# MilliNut.net
KiCad netlist of a schematic drawn in Altium Designer
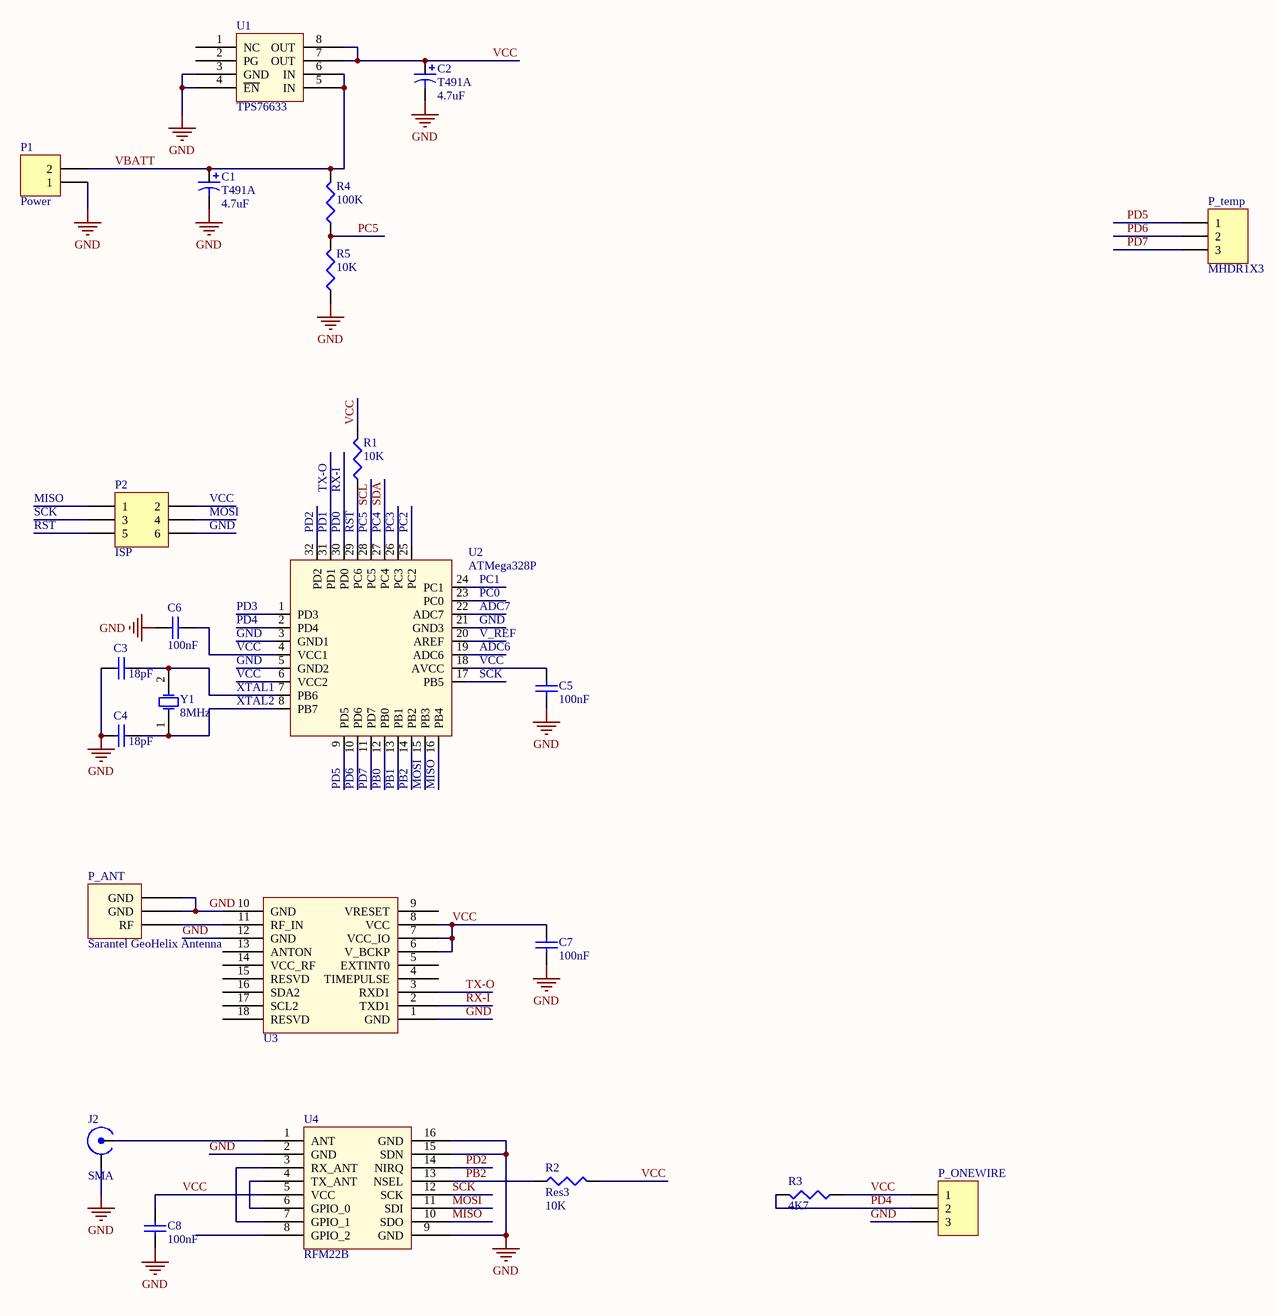
[diagram p0: MilliNut.SchDoc]

(export (version "E")
  (design (tool "Eeschema 10.0.6"))
  (components
    (comp (ref "C1")
      (value "T491A")
      (footprint "Kemet T491A")
      (description "Solid Tantalum Chip Capacitor, Standard T491 Series - Industrial Grade")
      (fields (field (name "ALTIUM_VALUE") "4.7uF") (field (name "PUBLISHER") "Altium Limited"))
      (libsource (lib "KEMET Chip Capacitor") (part "T491A"))
    )
    (comp (ref "C2")
      (value "T491A")
      (footprint "Kemet T491A")
      (description "Solid Tantalum Chip Capacitor, Standard T491 Series - Industrial Grade")
      (fields (field (name "ALTIUM_VALUE") "4.7uF") (field (name "PUBLISHER") "Altium Limited"))
      (libsource (lib "KEMET Chip Capacitor") (part "T491A"))
    )
    (comp (ref "C3")
      (value "18pF")
      (footprint "1608[0603]")
      (description "Ceramic Chip Capacitor - Standard")
      (fields (field (name "Comment") "C0805") (field (name "PUBLISHER") "Altium Limited"))
      (libsource (lib "KEMET Chip Capacitor") (part "C0805"))
    )
    (comp (ref "C4")
      (value "18pF")
      (footprint "1608[0603]")
      (description "Ceramic Chip Capacitor - Standard")
      (fields (field (name "Comment") "C0805") (field (name "PUBLISHER") "Altium Limited"))
      (libsource (lib "KEMET Chip Capacitor") (part "C0805"))
    )
    (comp (ref "C5")
      (value "100nF")
      (footprint "1608[0603]")
      (description "Capacitor (Semiconductor SIM Model)")
      (fields (field (name "Comment") "Cap Semi") (field (name "PUBLISHER") "Altium Limited"))
      (libsource (lib "Miscellaneous Devices") (part "Cap Semi"))
    )
    (comp (ref "C6")
      (value "100nF")
      (footprint "1608[0603]")
      (description "Capacitor (Semiconductor SIM Model)")
      (fields (field (name "Comment") "Cap Semi") (field (name "PUBLISHER") "Altium Limited"))
      (libsource (lib "Miscellaneous Devices") (part "Cap Semi"))
    )
    (comp (ref "C7")
      (value "100nF")
      (footprint "1608[0603]")
      (description "Capacitor (Semiconductor SIM Model)")
      (fields (field (name "Comment") "Cap Semi") (field (name "PUBLISHER") "Altium Limited"))
      (libsource (lib "Miscellaneous Devices") (part "Cap Semi"))
    )
    (comp (ref "C8")
      (value "100nF")
      (footprint "1608[0603]")
      (description "Capacitor (Semiconductor SIM Model)")
      (fields (field (name "Comment") "Cap Semi") (field (name "PUBLISHER") "Altium Limited"))
      (libsource (lib "Miscellaneous Devices") (part "Cap Semi"))
    )
    (comp (ref "J2")
      (value "SMA")
      (footprint "Darkside_Lib:CON SMA PCB 90")
      (description "Power Connector")
      (fields (field (name "Comment") "SMA_L"))
      (libsource (lib "Darkside_Lib") (part "SMA_L"))
    )
    (comp (ref "P1")
      (value "Power")
      (footprint "HDR1X2")
      (description "Header, 2-Pin")
      (fields (field (name "PUBLISHER") "Altium Limited"))
      (libsource (lib "Miscellaneous Connectors") (part "Header 2"))
    )
    (comp (ref "P2")
      (value "ISP")
      (footprint "HDR2X3")
      (description "Header, 3-Pin, Dual row")
      (fields (field (name "PUBLISHER") "Altium Limited"))
      (libsource (lib "Miscellaneous Connectors") (part "Header 3X2"))
    )
    (comp (ref "P_ANT")
      (value "Sarantel GeoHelix Antenna")
      (footprint "Darkside_Lib:Sarantel SL1202RH")
      (libsource (lib "Darkside_Lib") (part "Sarantel GeoHelix Antenna"))
    )
    (comp (ref "P_ONEWIRE")
      (value "Header 3")
      (footprint "HDR1X3")
      (description "Header, 3-Pin")
      (fields (field (name "PUBLISHER") "Altium Limited"))
      (libsource (lib "Miscellaneous Connectors") (part "Header 3"))
    )
    (comp (ref "P_temp")
      (value "MHDR1X3")
      (footprint "MHDR1X3")
      (description "Header, 3-Pin")
      (fields (field (name "PUBLISHER") "Altium Limited"))
      (libsource (lib "Miscellaneous Connectors") (part "MHDR1X3"))
    )
    (comp (ref "R1")
      (value "10K")
      (footprint "1608[0603]")
      (description "Resistor")
      (fields (field (name "Comment") "Res3") (field (name "PUBLISHER") "Altium Limited"))
      (libsource (lib "Miscellaneous Devices") (part "Res3"))
    )
    (comp (ref "R2")
      (value "Res3")
      (footprint "J1-0603")
      (description "Resistor")
      (fields (field (name "ALTIUM_VALUE") "10K") (field (name "PUBLISHER") "Altium Limited"))
      (libsource (lib "Miscellaneous Devices") (part "Res3"))
    )
    (comp (ref "R3")
      (value "4K7")
      (footprint "J1-0603")
      (description "Resistor")
      (fields (field (name "Comment") "Res3") (field (name "PUBLISHER") "Altium Limited"))
      (libsource (lib "Miscellaneous Devices") (part "Res3"))
    )
    (comp (ref "R4")
      (value "100K")
      (footprint "J1-0603")
      (description "Resistor")
      (fields (field (name "Comment") "Res3") (field (name "PUBLISHER") "Altium Limited"))
      (libsource (lib "Miscellaneous Devices") (part "Res3"))
    )
    (comp (ref "R5")
      (value "10K")
      (footprint "J1-0603")
      (description "Resistor")
      (fields (field (name "Comment") "Res3") (field (name "PUBLISHER") "Altium Limited"))
      (libsource (lib "Miscellaneous Devices") (part "Res3"))
    )
    (comp (ref "U1")
      (value "TPS76633")
      (footprint "TPS76633")
      (libsource (lib "Darkside_Lib") (part "TPS76633"))
    )
    (comp (ref "U2")
      (value "ATMega328P")
      (footprint "Darkside_Lib:TQFP32")
      (libsource (lib "Darkside_Lib") (part "ATMega328P"))
    )
    (comp (ref "U3")
      (value "uBlox MAX-6Q")
      (footprint "MAX-6Q")
      (libsource (lib "Darkside_Lib") (part "uBlox MAX-6Q"))
    )
    (comp (ref "U4")
      (value "RFM22B")
      (footprint "RFM22B")
      (libsource (lib "Darkside_Lib") (part "RFM22B-S2"))
    )
    (comp (ref "Y1")
      (value "8MHz")
      (footprint "ABM3_XTAL")
      (description "Crystal Oscillator")
      (fields (field (name "PUBLISHER") "Altium Limited"))
      (libsource (lib "ECS Crystal Oscillator") (part "ECS-110-S-1"))
    )
  )
  (nets
    (net (code "1") (name "/ADC6") (class "Default")
      (node (ref "U2") (pin "19") (pinfunction "ADC6_19") (pintype "passive"))
    )
    (net (code "2") (name "/ADC7") (class "Default")
      (node (ref "U2") (pin "22") (pinfunction "ADC7_22") (pintype "passive"))
    )
    (net (code "3") (name "/MISO") (class "Default")
      (node (ref "P2") (pin "1") (pinfunction "1_1") (pintype "passive"))
      (node (ref "U2") (pin "16") (pinfunction "PB4_16") (pintype "passive"))
      (node (ref "U4") (pin "10") (pinfunction "SDO_10") (pintype "passive"))
    )
    (net (code "4") (name "/MOSI") (class "Default")
      (node (ref "P2") (pin "4") (pinfunction "4_4") (pintype "passive"))
      (node (ref "U2") (pin "15") (pinfunction "PB3_15") (pintype "passive"))
      (node (ref "U4") (pin "11") (pinfunction "SDI_11") (pintype "passive"))
    )
    (net (code "5") (name "/PB0") (class "Default")
      (node (ref "U2") (pin "12") (pinfunction "PB0_12") (pintype "passive"))
    )
    (net (code "6") (name "/PB1") (class "Default")
      (node (ref "U2") (pin "13") (pinfunction "PB1_13") (pintype "passive"))
    )
    (net (code "7") (name "/PB2") (class "Default")
      (node (ref "R2") (pin "1") (pinfunction "1_1") (pintype "passive"))
      (node (ref "U2") (pin "14") (pinfunction "PB2_14") (pintype "passive"))
      (node (ref "U4") (pin "13") (pinfunction "NSEL_13") (pintype "passive"))
    )
    (net (code "8") (name "/PC0") (class "Default")
      (node (ref "U2") (pin "23") (pinfunction "PC0_23") (pintype "passive"))
    )
    (net (code "9") (name "/PC1") (class "Default")
      (node (ref "U2") (pin "24") (pinfunction "PC1_24") (pintype "passive"))
    )
    (net (code "10") (name "/PC2") (class "Default")
      (node (ref "U2") (pin "25") (pinfunction "PC2_25") (pintype "passive"))
    )
    (net (code "11") (name "/PC3") (class "Default")
      (node (ref "U2") (pin "26") (pinfunction "PC3_26") (pintype "passive"))
    )
    (net (code "12") (name "/PC4") (class "Default")
      (node (ref "U2") (pin "27") (pinfunction "PC4_27") (pintype "passive"))
    )
    (net (code "13") (name "/PC5") (class "Default")
      (node (ref "R4") (pin "1") (pinfunction "1_1") (pintype "passive"))
      (node (ref "R5") (pin "2") (pinfunction "2_2") (pintype "passive"))
      (node (ref "U2") (pin "28") (pinfunction "PC5_28") (pintype "passive"))
    )
    (net (code "14") (name "/PD0") (class "Default")
      (node (ref "U2") (pin "30") (pinfunction "PD0_30") (pintype "passive"))
      (node (ref "U3") (pin "2") (pinfunction "TXD1_2") (pintype "passive"))
    )
    (net (code "15") (name "/PD1") (class "Default")
      (node (ref "U2") (pin "31") (pinfunction "PD1_31") (pintype "passive"))
      (node (ref "U3") (pin "3") (pinfunction "RXD1_3") (pintype "passive"))
    )
    (net (code "16") (name "/PD2") (class "Default")
      (node (ref "U2") (pin "32") (pinfunction "PD2_32") (pintype "passive"))
      (node (ref "U4") (pin "14") (pinfunction "NIRQ_14") (pintype "passive"))
    )
    (net (code "17") (name "/PD3") (class "Default")
      (node (ref "U2") (pin "1") (pinfunction "PD3_1") (pintype "passive"))
    )
    (net (code "18") (name "/PD4") (class "Default")
      (node (ref "P_ONEWIRE") (pin "2") (pinfunction "2_2") (pintype "passive"))
      (node (ref "R3") (pin "2") (pinfunction "2_2") (pintype "passive"))
      (node (ref "U2") (pin "2") (pinfunction "PD4_2") (pintype "passive"))
    )
    (net (code "19") (name "/PD5") (class "Default")
      (node (ref "P_temp") (pin "1") (pinfunction "1_1") (pintype "passive"))
      (node (ref "U2") (pin "9") (pinfunction "PD5_9") (pintype "passive"))
    )
    (net (code "20") (name "/PD6") (class "Default")
      (node (ref "P_temp") (pin "2") (pinfunction "2_2") (pintype "passive"))
      (node (ref "U2") (pin "10") (pinfunction "PD6_10") (pintype "passive"))
    )
    (net (code "21") (name "/PD7") (class "Default")
      (node (ref "P_temp") (pin "3") (pinfunction "3_3") (pintype "passive"))
      (node (ref "U2") (pin "11") (pinfunction "PD7_11") (pintype "passive"))
    )
    (net (code "22") (name "/RST") (class "Default")
      (node (ref "P2") (pin "5") (pinfunction "5_5") (pintype "passive"))
      (node (ref "R1") (pin "1") (pinfunction "1_1") (pintype "passive"))
      (node (ref "U2") (pin "29") (pinfunction "PC6_29") (pintype "passive"))
    )
    (net (code "23") (name "/SCK") (class "Default")
      (node (ref "P2") (pin "3") (pinfunction "3_3") (pintype "passive"))
      (node (ref "U2") (pin "17") (pinfunction "PB5_17") (pintype "passive"))
      (node (ref "U4") (pin "12") (pinfunction "SCK_12") (pintype "passive"))
    )
    (net (code "24") (name "/VBATT") (class "Default")
      (node (ref "C1") (pin "1") (pinfunction "1_1") (pintype "passive"))
      (node (ref "P1") (pin "2") (pinfunction "2_2") (pintype "passive"))
      (node (ref "R4") (pin "2") (pinfunction "2_2") (pintype "passive"))
      (node (ref "U1") (pin "5") (pinfunction "IN_5") (pintype "passive"))
      (node (ref "U1") (pin "6") (pinfunction "IN_6") (pintype "passive"))
    )
    (net (code "25") (name "/VCC") (class "Default")
      (node (ref "C2") (pin "1") (pinfunction "1_1") (pintype "passive"))
      (node (ref "C5") (pin "2") (pinfunction "2_2") (pintype "passive"))
      (node (ref "C6") (pin "2") (pinfunction "2_2") (pintype "passive"))
      (node (ref "C7") (pin "2") (pinfunction "2_2") (pintype "passive"))
      (node (ref "C8") (pin "2") (pinfunction "2_2") (pintype "passive"))
      (node (ref "P2") (pin "2") (pinfunction "2_2") (pintype "passive"))
      (node (ref "P_ONEWIRE") (pin "1") (pinfunction "1_1") (pintype "passive"))
      (node (ref "R1") (pin "2") (pinfunction "2_2") (pintype "passive"))
      (node (ref "R2") (pin "2") (pinfunction "2_2") (pintype "passive"))
      (node (ref "R3") (pin "1") (pinfunction "1_1") (pintype "passive"))
      (node (ref "U1") (pin "7") (pinfunction "OUT_7") (pintype "passive"))
      (node (ref "U1") (pin "8") (pinfunction "OUT_8") (pintype "passive"))
      (node (ref "U2") (pin "18") (pinfunction "AVCC_18") (pintype "passive"))
      (node (ref "U2") (pin "4") (pinfunction "VCC1_4") (pintype "passive"))
      (node (ref "U2") (pin "6") (pinfunction "VCC2_6") (pintype "passive"))
      (node (ref "U3") (pin "6") (pinfunction "V_BCKP_6") (pintype "passive"))
      (node (ref "U3") (pin "7") (pinfunction "VCC_IO_7") (pintype "passive"))
      (node (ref "U3") (pin "8") (pinfunction "VCC_8") (pintype "passive"))
      (node (ref "U4") (pin "5") (pinfunction "VCC_5") (pintype "passive"))
    )
    (net (code "26") (name "/V_REF") (class "Default")
      (node (ref "U2") (pin "20") (pinfunction "AREF_20") (pintype "passive"))
    )
    (net (code "27") (name "/XTAL1") (class "Default")
      (node (ref "C3") (pin "2") (pinfunction "2_2") (pintype "passive"))
      (node (ref "U2") (pin "7") (pinfunction "PB6_7") (pintype "passive"))
      (node (ref "Y1") (pin "2") (pinfunction "OSC2_2") (pintype "passive"))
    )
    (net (code "28") (name "/XTAL2") (class "Default")
      (node (ref "C4") (pin "2") (pinfunction "2_2") (pintype "passive"))
      (node (ref "U2") (pin "8") (pinfunction "PB7_8") (pintype "passive"))
      (node (ref "Y1") (pin "1") (pinfunction "OSC1_1") (pintype "passive"))
    )
    (net (code "29") (name "GND") (class "Default")
      (node (ref "C1") (pin "2") (pinfunction "2_2") (pintype "passive"))
      (node (ref "C2") (pin "2") (pinfunction "2_2") (pintype "passive"))
      (node (ref "C3") (pin "1") (pinfunction "1_1") (pintype "passive"))
      (node (ref "C4") (pin "1") (pinfunction "1_1") (pintype "passive"))
      (node (ref "C5") (pin "1") (pinfunction "1_1") (pintype "passive"))
      (node (ref "C6") (pin "1") (pinfunction "1_1") (pintype "passive"))
      (node (ref "C7") (pin "1") (pinfunction "1_1") (pintype "passive"))
      (node (ref "C8") (pin "1") (pinfunction "1_1") (pintype "passive"))
      (node (ref "J2") (pin "2") (pinfunction "2_2") (pintype "passive"))
      (node (ref "P1") (pin "1") (pinfunction "1_1") (pintype "passive"))
      (node (ref "P2") (pin "6") (pinfunction "6_6") (pintype "passive"))
      (node (ref "P_ANT") (pin "2") (pinfunction "GND_2") (pintype "passive"))
      (node (ref "P_ANT") (pin "3") (pinfunction "GND_3") (pintype "passive"))
      (node (ref "P_ONEWIRE") (pin "3") (pinfunction "3_3") (pintype "passive"))
      (node (ref "R5") (pin "1") (pinfunction "1_1") (pintype "passive"))
      (node (ref "U1") (pin "3") (pinfunction "GND_3") (pintype "passive"))
      (node (ref "U1") (pin "4") (pinfunction "~{EN}_4") (pintype "passive"))
      (node (ref "U2") (pin "21") (pinfunction "GND3_21") (pintype "passive"))
      (node (ref "U2") (pin "3") (pinfunction "GND1_3") (pintype "passive"))
      (node (ref "U2") (pin "5") (pinfunction "GND2_5") (pintype "passive"))
      (node (ref "U3") (pin "1") (pinfunction "GND_1") (pintype "passive"))
      (node (ref "U3") (pin "10") (pinfunction "GND_10") (pintype "passive"))
      (node (ref "U3") (pin "12") (pinfunction "GND_12") (pintype "passive"))
      (node (ref "U4") (pin "15") (pinfunction "SDN_15") (pintype "passive"))
      (node (ref "U4") (pin "16") (pinfunction "GND_16") (pintype "passive"))
      (node (ref "U4") (pin "2") (pinfunction "GND_2") (pintype "passive"))
      (node (ref "U4") (pin "9") (pinfunction "GND_9") (pintype "passive"))
    )
    (net (code "30") (name "Net-(P_ANT-RF)") (class "Default")
      (node (ref "P_ANT") (pin "1") (pinfunction "RF_1") (pintype "passive"))
      (node (ref "U3") (pin "11") (pinfunction "RF_IN_11") (pintype "passive"))
    )
    (net (code "31") (name "Net-(U4-ANT)") (class "Default")
      (node (ref "J2") (pin "1") (pinfunction "1_1") (pintype "passive"))
      (node (ref "U4") (pin "1") (pinfunction "ANT_1") (pintype "passive"))
    )
    (net (code "32") (name "Net-(U4-GPIO_0)") (class "Default")
      (node (ref "U4") (pin "4") (pinfunction "TX_ANT_4") (pintype "passive"))
      (node (ref "U4") (pin "6") (pinfunction "GPIO_0_6") (pintype "passive"))
    )
    (net (code "33") (name "Net-(U4-GPIO_1)") (class "Default")
      (node (ref "U4") (pin "3") (pinfunction "RX_ANT_3") (pintype "passive"))
      (node (ref "U4") (pin "7") (pinfunction "GPIO_1_7") (pintype "passive"))
    )
    (net (code "34") (name "unconnected-(U1-NC-Pad1)") (class "Default")
      (node (ref "U1") (pin "1") (pinfunction "NC_1") (pintype "passive"))
    )
    (net (code "35") (name "unconnected-(U1-PG-Pad2)") (class "Default")
      (node (ref "U1") (pin "2") (pinfunction "PG_2") (pintype "passive"))
    )
    (net (code "36") (name "unconnected-(U3-ANTON-Pad13)") (class "Default")
      (node (ref "U3") (pin "13") (pinfunction "ANTON_13") (pintype "passive"))
    )
    (net (code "37") (name "unconnected-(U3-EXTINT0-Pad5)") (class "Default")
      (node (ref "U3") (pin "5") (pinfunction "EXTINT0_5") (pintype "passive"))
    )
    (net (code "38") (name "unconnected-(U3-RESVD-Pad15)") (class "Default")
      (node (ref "U3") (pin "15") (pinfunction "RESVD_15") (pintype "passive"))
    )
    (net (code "39") (name "unconnected-(U3-RESVD-Pad18)") (class "Default")
      (node (ref "U3") (pin "18") (pinfunction "RESVD_18") (pintype "passive"))
    )
    (net (code "40") (name "unconnected-(U3-SCL2-Pad17)") (class "Default")
      (node (ref "U3") (pin "17") (pinfunction "SCL2_17") (pintype "passive"))
    )
    (net (code "41") (name "unconnected-(U3-SDA2-Pad16)") (class "Default")
      (node (ref "U3") (pin "16") (pinfunction "SDA2_16") (pintype "passive"))
    )
    (net (code "42") (name "unconnected-(U3-TIMEPULSE-Pad4)") (class "Default")
      (node (ref "U3") (pin "4") (pinfunction "TIMEPULSE_4") (pintype "passive"))
    )
    (net (code "43") (name "unconnected-(U3-VCC_RF-Pad14)") (class "Default")
      (node (ref "U3") (pin "14") (pinfunction "VCC_RF_14") (pintype "passive"))
    )
    (net (code "44") (name "unconnected-(U3-VRESET-Pad9)") (class "Default")
      (node (ref "U3") (pin "9") (pinfunction "VRESET_9") (pintype "passive"))
    )
    (net (code "45") (name "unconnected-(U4-GPIO_2-Pad8)") (class "Default")
      (node (ref "U4") (pin "8") (pinfunction "GPIO_2_8") (pintype "passive"))
    )
  )
)
